# schematicCharger.net
KiCad netlist of a schematic drawn in Altium Designer
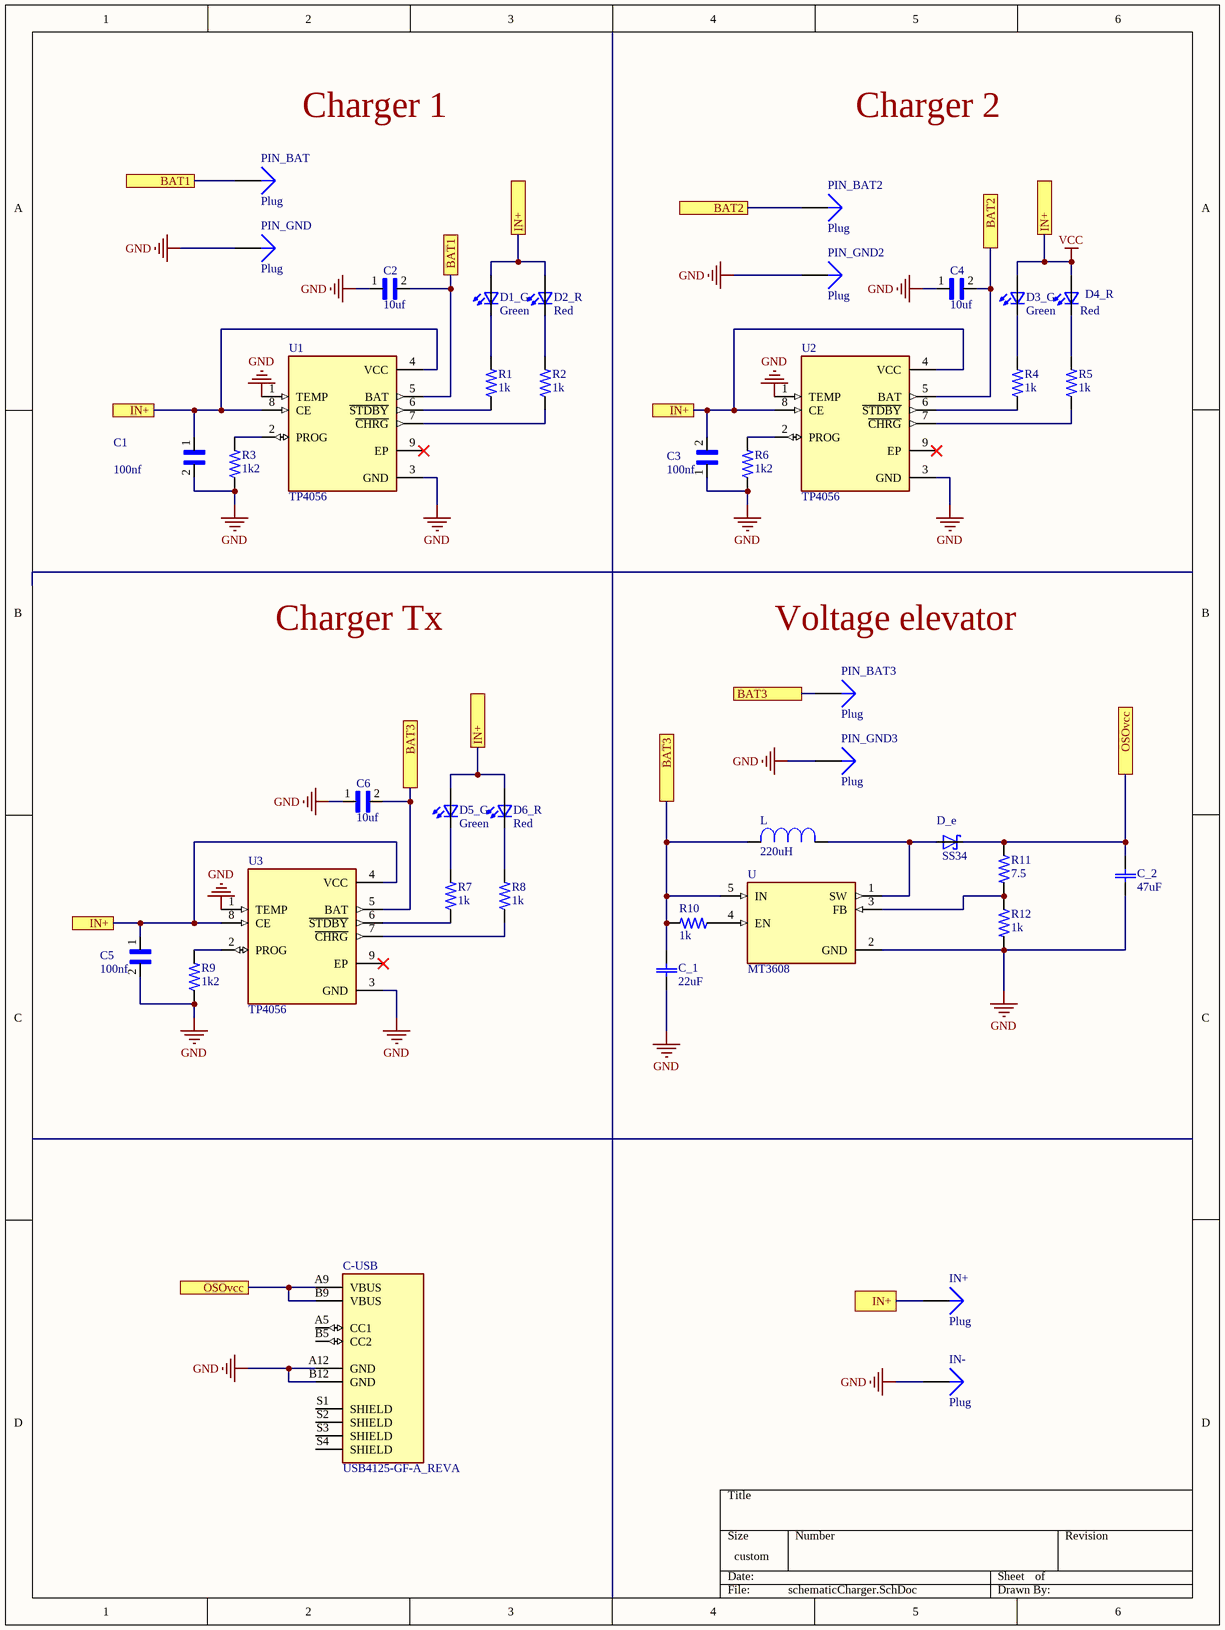
[diagram p0: schematicCharger.SchDoc]

(export (version "E")
  (design (tool "Eeschema 10.0.6"))
  (components
    (comp (ref "C-USB")
      (value "USB4125-GF-A_REVA")
      (footprint "GCT_USB4125-GF-A_REVA")
      (description "USB 2.0 Type C Receptacle, Horizontal, SMT, For Power charging")
      (fields (field (name "MP") "USB4125-GF-A") (field (name "MF") "Global Connector Technology"))
      (libsource (lib "TipoC") (part "USB4125-GF-A_REVA"))
    )
    (comp (ref "C1")
      (value "100nf")
      (footprint "CAPC1608X90")
      (description "0.1ÂµF Â±10% 50V Ceramic Capacitor X7R 0603 _1608 Metric_")
      (fields (field (name "DIGI-KEY_PART_NUMBER") "311-1344-1-ND") (field (name "MP") "CC0603KRX7R9BB104"))
      (libsource (lib "") (part "CC0603KRX7R9BB104_2"))
    )
    (comp (ref "C2")
      (value "10uf")
      (footprint "CAPC1608X90")
      (description "0.1ÂµF Â±10% 50V Ceramic Capacitor X7R 0603 _1608 Metric_")
      (fields (field (name "DIGI-KEY_PART_NUMBER") "311-1344-1-ND") (field (name "MP") "CC0603KRX7R9BB104"))
      (libsource (lib "capacitor0603") (part "CC0603KRX7R9BB104"))
    )
    (comp (ref "C3")
      (value "100nf")
      (footprint "CAPC1608X90")
      (description "0.1ÂµF Â±10% 50V Ceramic Capacitor X7R 0603 _1608 Metric_")
      (fields (field (name "DIGI-KEY_PART_NUMBER") "311-1344-1-ND") (field (name "MP") "CC0603KRX7R9BB104"))
      (libsource (lib "") (part "CC0603KRX7R9BB104_1"))
    )
    (comp (ref "C4")
      (value "10uf")
      (footprint "CAPC1608X90")
      (description "0.1ÂµF Â±10% 50V Ceramic Capacitor X7R 0603 _1608 Metric_")
      (fields (field (name "DIGI-KEY_PART_NUMBER") "311-1344-1-ND") (field (name "MP") "CC0603KRX7R9BB104"))
      (libsource (lib "capacitor0603") (part "CC0603KRX7R9BB104"))
    )
    (comp (ref "C5")
      (value "100nf")
      (footprint "CAPC1608X90")
      (description "0.1ÂµF Â±10% 50V Ceramic Capacitor X7R 0603 _1608 Metric_")
      (fields (field (name "DIGI-KEY_PART_NUMBER") "311-1344-1-ND") (field (name "MP") "CC0603KRX7R9BB104"))
      (libsource (lib "") (part "CC0603KRX7R9BB104_2"))
    )
    (comp (ref "C6")
      (value "10uf")
      (footprint "CAPC1608X90")
      (description "0.1ÂµF Â±10% 50V Ceramic Capacitor X7R 0603 _1608 Metric_")
      (fields (field (name "DIGI-KEY_PART_NUMBER") "311-1344-1-ND") (field (name "MP") "CC0603KRX7R9BB104"))
      (libsource (lib "capacitor0603") (part "CC0603KRX7R9BB104"))
    )
    (comp (ref "C_1")
      (value "22uF")
      (footprint "CAPC4532X254N")
      (description "0.33ÂµF Â±10% 250V Ceramic Capacitor X7R 1812 (4532 Metric)")
      (fields (field (name "MF") "AVX") (field (name "MP") "1812PC334KAT1A"))
      (libsource (lib "1812_CAP") (part "1812PC334KAT1A"))
    )
    (comp (ref "C_2")
      (value "47uF")
      (footprint "CAPC4532X254N")
      (description "0.33ÂµF Â±10% 250V Ceramic Capacitor X7R 1812 (4532 Metric)")
      (fields (field (name "MF") "AVX") (field (name "MP") "1812PC334KAT1A"))
      (libsource (lib "1812_CAP") (part "1812PC334KAT1A"))
    )
    (comp (ref "D1_G")
      (value "Green")
      (footprint "0603gree")
      (description "Green 571nm LED Indication - Discrete 2V 0603 _1608 Metric_")
      (fields (field (name "MF") "Lite-On Inc.") (field (name "MP") "LTST-C191KGKT"))
      (libsource (lib "LedVerde") (part "LTST-C191KGKT"))
    )
    (comp (ref "D2_R")
      (value "Red")
      (footprint "0603red")
      (description "Green 571nm LED Indication - Discrete 2V 0603 _1608 Metric_")
      (fields (field (name "MF") "Lite-On Inc.") (field (name "MP") "LTST-C191KGKT"))
      (libsource (lib "LedRojo") (part "LTST-C191KGKT"))
    )
    (comp (ref "D3_G")
      (value "Green")
      (footprint "0603gree")
      (description "Green 571nm LED Indication - Discrete 2V 0603 _1608 Metric_")
      (fields (field (name "MF") "Lite-On Inc.") (field (name "MP") "LTST-C191KGKT"))
      (libsource (lib "LedVerde") (part "LTST-C191KGKT"))
    )
    (comp (ref "D4_R")
      (value "Red")
      (footprint "0603red")
      (description "Green 571nm LED Indication - Discrete 2V 0603 _1608 Metric_")
      (fields (field (name "MF") "Lite-On Inc.") (field (name "MP") "LTST-C191KGKT"))
      (libsource (lib "LedRojo") (part "LTST-C191KGKT"))
    )
    (comp (ref "D5_G")
      (value "Green")
      (footprint "0603gree")
      (description "Green 571nm LED Indication - Discrete 2V 0603 _1608 Metric_")
      (fields (field (name "MF") "Lite-On Inc.") (field (name "MP") "LTST-C191KGKT"))
      (libsource (lib "LedVerde") (part "LTST-C191KGKT"))
    )
    (comp (ref "D6_R")
      (value "Red")
      (footprint "0603red")
      (description "Green 571nm LED Indication - Discrete 2V 0603 _1608 Metric_")
      (fields (field (name "MF") "Lite-On Inc.") (field (name "MP") "LTST-C191KGKT"))
      (libsource (lib "LedRojo") (part "LTST-C191KGKT"))
    )
    (comp (ref "D_e")
      (value "SS34")
      (footprint "DIOM6859X262N")
      (fields (field (name "MF") "ON Semiconductor"))
      (libsource (lib "ss34v3") (part "SS34"))
    )
    (comp (ref "IN+")
      (value "Plug")
      (footprint "PIN1")
      (fields (field (name "PUBLISHER") "Altium Limited"))
      (libsource (lib "Miscellaneous Connectors") (part "Plug"))
    )
    (comp (ref "IN-")
      (value "Plug")
      (footprint "PIN1")
      (fields (field (name "PUBLISHER") "Altium Limited"))
      (libsource (lib "Miscellaneous Connectors") (part "Plug"))
    )
    (comp (ref "L")
      (value "220uH")
      (footprint "INDM7676X435N")
      (description "2.2ÂµH Shielded Wirewound Inductor 4.76A 12.6mOhm Nonstandard")
      (fields (field (name "MP") "DR74-2R2-R") (field (name "MF") "Eaton"))
      (libsource (lib "Bobina220") (part "DR74-2R2-R"))
    )
    (comp (ref "PIN_BAT")
      (value "Plug")
      (footprint "PIN1")
      (fields (field (name "PUBLISHER") "Altium Limited"))
      (libsource (lib "Miscellaneous Connectors") (part "Plug"))
    )
    (comp (ref "PIN_BAT2")
      (value "Plug")
      (footprint "PIN1")
      (fields (field (name "PUBLISHER") "Altium Limited"))
      (libsource (lib "Miscellaneous Connectors") (part "Plug"))
    )
    (comp (ref "PIN_BAT3")
      (value "Plug")
      (footprint "PIN1")
      (fields (field (name "PUBLISHER") "Altium Limited"))
      (libsource (lib "Miscellaneous Connectors") (part "Plug"))
    )
    (comp (ref "PIN_GND")
      (value "Plug")
      (footprint "PIN1")
      (fields (field (name "PUBLISHER") "Altium Limited"))
      (libsource (lib "Miscellaneous Connectors") (part "Plug"))
    )
    (comp (ref "PIN_GND2")
      (value "Plug")
      (footprint "PIN1")
      (fields (field (name "PUBLISHER") "Altium Limited"))
      (libsource (lib "Miscellaneous Connectors") (part "Plug"))
    )
    (comp (ref "PIN_GND3")
      (value "Plug")
      (footprint "PIN1")
      (fields (field (name "PUBLISHER") "Altium Limited"))
      (libsource (lib "Miscellaneous Connectors") (part "Plug"))
    )
    (comp (ref "R1")
      (value "1k")
      (footprint "RESC1608X50N")
      (description "Res, Thin Film, 13r, 0.1%, 0.1w, 0603")
      (fields (field (name "MP") "RP73D1J13RBTDG") (field (name "MF") "TE Connectivity"))
      (libsource (lib "Res0603") (part "RP73D1J13RBTDG"))
    )
    (comp (ref "R2")
      (value "1k")
      (footprint "RESC1608X50N")
      (description "Res, Thin Film, 13r, 0.1%, 0.1w, 0603")
      (fields (field (name "MP") "RP73D1J13RBTDG") (field (name "MF") "TE Connectivity"))
      (libsource (lib "Res0603") (part "RP73D1J13RBTDG"))
    )
    (comp (ref "R3")
      (value "1k2")
      (footprint "RESC1608X50N")
      (description "Res, Thin Film, 13r, 0.1%, 0.1w, 0603")
      (fields (field (name "MP") "RP73D1J13RBTDG") (field (name "MF") "TE Connectivity"))
      (libsource (lib "Res0603") (part "RP73D1J13RBTDG"))
    )
    (comp (ref "R4")
      (value "1k")
      (footprint "RESC1608X50N")
      (description "Res, Thin Film, 13r, 0.1%, 0.1w, 0603")
      (fields (field (name "MP") "RP73D1J13RBTDG") (field (name "MF") "TE Connectivity"))
      (libsource (lib "Res0603") (part "RP73D1J13RBTDG"))
    )
    (comp (ref "R5")
      (value "1k")
      (footprint "RESC1608X50N")
      (description "Res, Thin Film, 13r, 0.1%, 0.1w, 0603")
      (fields (field (name "MP") "RP73D1J13RBTDG") (field (name "MF") "TE Connectivity"))
      (libsource (lib "Res0603") (part "RP73D1J13RBTDG"))
    )
    (comp (ref "R6")
      (value "1k2")
      (footprint "RESC1608X50N")
      (description "Res, Thin Film, 13r, 0.1%, 0.1w, 0603")
      (fields (field (name "MP") "RP73D1J13RBTDG") (field (name "MF") "TE Connectivity"))
      (libsource (lib "Res0603") (part "RP73D1J13RBTDG"))
    )
    (comp (ref "R7")
      (value "1k")
      (footprint "RESC1608X50N")
      (description "Res, Thin Film, 13r, 0.1%, 0.1w, 0603")
      (fields (field (name "MP") "RP73D1J13RBTDG") (field (name "MF") "TE Connectivity"))
      (libsource (lib "Res0603") (part "RP73D1J13RBTDG"))
    )
    (comp (ref "R8")
      (value "1k")
      (footprint "RESC1608X50N")
      (description "Res, Thin Film, 13r, 0.1%, 0.1w, 0603")
      (fields (field (name "MP") "RP73D1J13RBTDG") (field (name "MF") "TE Connectivity"))
      (libsource (lib "Res0603") (part "RP73D1J13RBTDG"))
    )
    (comp (ref "R9")
      (value "1k2")
      (footprint "RESC1608X50N")
      (description "Res, Thin Film, 13r, 0.1%, 0.1w, 0603")
      (fields (field (name "MP") "RP73D1J13RBTDG") (field (name "MF") "TE Connectivity"))
      (libsource (lib "Res0603") (part "RP73D1J13RBTDG"))
    )
    (comp (ref "R10")
      (value "1k")
      (footprint "RESC1608X50N")
      (description "Res, Thin Film, 13r, 0.1%, 0.1w, 0603")
      (fields (field (name "MP") "RP73D1J13RBTDG") (field (name "MF") "TE Connectivity"))
      (libsource (lib "Res0603") (part "RP73D1J13RBTDG"))
    )
    (comp (ref "R11")
      (value "7.5")
      (footprint "RESC1608X50N")
      (description "Res, Thin Film, 13r, 0.1%, 0.1w, 0603")
      (fields (field (name "MP") "RP73D1J13RBTDG") (field (name "MF") "TE Connectivity"))
      (libsource (lib "Res0603") (part "RP73D1J13RBTDG"))
    )
    (comp (ref "R12")
      (value "1k")
      (footprint "RESC1608X50N")
      (description "Res, Thin Film, 13r, 0.1%, 0.1w, 0603")
      (fields (field (name "MP") "RP73D1J13RBTDG") (field (name "MF") "TE Connectivity"))
      (libsource (lib "Res0603") (part "RP73D1J13RBTDG"))
    )
    (comp (ref "U")
      (value "MT3608")
      (footprint "SOT95P280X145-6N")
      (description "High Efficiency 1.2MHz2A Step Up Converter")
      (fields (field (name "MF") "Aerosemi Technology Co., Ltd"))
      (libsource (lib "MT3608") (part "MT3608"))
    )
    (comp (ref "U1")
      (value "TP4056")
      (footprint "SOP127P600X175-9N")
      (description "Complete single cell Li-Ion battery with a constant current / constant voltage linear charger")
      (fields (field (name "MF") "NanJing Top Power ASIC Corp."))
      (libsource (lib "TP4056") (part "TP4056"))
    )
    (comp (ref "U2")
      (value "TP4056")
      (footprint "SOP127P600X175-9N")
      (description "Complete single cell Li-Ion battery with a constant current / constant voltage linear charger")
      (fields (field (name "MF") "NanJing Top Power ASIC Corp."))
      (libsource (lib "TP4056") (part "TP4056"))
    )
    (comp (ref "U3")
      (value "TP4056")
      (footprint "SOP127P600X175-9N")
      (description "Complete single cell Li-Ion battery with a constant current / constant voltage linear charger")
      (fields (field (name "MF") "NanJing Top Power ASIC Corp."))
      (libsource (lib "TP4056") (part "TP4056"))
    )
  )
  (nets
    (net (code "1") (name "/BAT1") (class "Default")
      (node (ref "C2") (pin "2") (pinfunction "2_2") (pintype "passive"))
      (node (ref "PIN_BAT") (pin "1") (pinfunction "1_1") (pintype "passive"))
      (node (ref "U1") (pin "5") (pinfunction "BAT_5") (pintype "output"))
    )
    (net (code "2") (name "/BAT2") (class "Default")
      (node (ref "C4") (pin "2") (pinfunction "2_2") (pintype "passive"))
      (node (ref "PIN_BAT2") (pin "1") (pinfunction "1_1") (pintype "passive"))
      (node (ref "U2") (pin "5") (pinfunction "BAT_5") (pintype "output"))
    )
    (net (code "3") (name "/BAT3") (class "Default")
      (node (ref "C6") (pin "2") (pinfunction "2_2") (pintype "passive"))
      (node (ref "C_1") (pin "2") (pinfunction "C2_2") (pintype "passive"))
      (node (ref "L") (pin "2") (pinfunction "2_2") (pintype "passive"))
      (node (ref "PIN_BAT3") (pin "1") (pinfunction "1_1") (pintype "passive"))
      (node (ref "R10") (pin "2") (pinfunction "2_2") (pintype "passive"))
      (node (ref "U") (pin "5") (pinfunction "IN_5") (pintype "input"))
      (node (ref "U3") (pin "5") (pinfunction "BAT_5") (pintype "output"))
    )
    (net (code "4") (name "/OSOvcc") (class "Default")
      (node (ref "C-USB") (pin "A9") (pinfunction "VBUS_A9") (pintype "power_in"))
      (node (ref "C-USB") (pin "B9") (pinfunction "VBUS_B9") (pintype "power_in"))
      (node (ref "C_2") (pin "2") (pinfunction "C2_2") (pintype "passive"))
      (node (ref "D_e") (pin "C") (pinfunction "C_C") (pintype "passive"))
      (node (ref "R11") (pin "1") (pinfunction "1_1") (pintype "passive"))
    )
    (net (code "5") (name "GND") (class "Default")
      (node (ref "C-USB") (pin "A12") (pinfunction "GND_A12") (pintype "power_in"))
      (node (ref "C-USB") (pin "B12") (pinfunction "GND_B12") (pintype "power_in"))
      (node (ref "C1") (pin "2") (pinfunction "2_2") (pintype "passive"))
      (node (ref "C2") (pin "1") (pinfunction "1_1") (pintype "passive"))
      (node (ref "C3") (pin "1") (pinfunction "1_1") (pintype "passive"))
      (node (ref "C4") (pin "1") (pinfunction "1_1") (pintype "passive"))
      (node (ref "C5") (pin "2") (pinfunction "2_2") (pintype "passive"))
      (node (ref "C6") (pin "1") (pinfunction "1_1") (pintype "passive"))
      (node (ref "C_1") (pin "1") (pinfunction "C1_1") (pintype "passive"))
      (node (ref "C_2") (pin "1") (pinfunction "C1_1") (pintype "passive"))
      (node (ref "IN-") (pin "1") (pinfunction "1_1") (pintype "passive"))
      (node (ref "PIN_GND") (pin "1") (pinfunction "1_1") (pintype "passive"))
      (node (ref "PIN_GND2") (pin "1") (pinfunction "1_1") (pintype "passive"))
      (node (ref "PIN_GND3") (pin "1") (pinfunction "1_1") (pintype "passive"))
      (node (ref "R12") (pin "2") (pinfunction "2_2") (pintype "passive"))
      (node (ref "R3") (pin "1") (pinfunction "1_1") (pintype "passive"))
      (node (ref "R6") (pin "1") (pinfunction "1_1") (pintype "passive"))
      (node (ref "R9") (pin "1") (pinfunction "1_1") (pintype "passive"))
      (node (ref "U") (pin "2") (pinfunction "GND_2") (pintype "power_in"))
      (node (ref "U1") (pin "1") (pinfunction "TEMP_1") (pintype "input"))
      (node (ref "U1") (pin "3") (pinfunction "GND_3") (pintype "power_in"))
      (node (ref "U2") (pin "1") (pinfunction "TEMP_1") (pintype "input"))
      (node (ref "U2") (pin "3") (pinfunction "GND_3") (pintype "power_in"))
      (node (ref "U3") (pin "1") (pinfunction "TEMP_1") (pintype "input"))
      (node (ref "U3") (pin "3") (pinfunction "GND_3") (pintype "power_in"))
    )
    (net (code "6") (name "Net-(D1_G-K2)") (class "Default")
      (node (ref "D1_G") (pin "1") (pinfunction "K2_1") (pintype "passive"))
      (node (ref "R1") (pin "2") (pinfunction "2_2") (pintype "passive"))
    )
    (net (code "7") (name "Net-(D2_R-K2)") (class "Default")
      (node (ref "D2_R") (pin "1") (pinfunction "K2_1") (pintype "passive"))
      (node (ref "R2") (pin "2") (pinfunction "2_2") (pintype "passive"))
    )
    (net (code "8") (name "Net-(D3_G-K2)") (class "Default")
      (node (ref "D3_G") (pin "1") (pinfunction "K2_1") (pintype "passive"))
      (node (ref "R4") (pin "2") (pinfunction "2_2") (pintype "passive"))
    )
    (net (code "9") (name "Net-(D4_R-K2)") (class "Default")
      (node (ref "D4_R") (pin "1") (pinfunction "K2_1") (pintype "passive"))
      (node (ref "R5") (pin "2") (pinfunction "2_2") (pintype "passive"))
    )
    (net (code "10") (name "Net-(D5_G-K2)") (class "Default")
      (node (ref "D5_G") (pin "1") (pinfunction "K2_1") (pintype "passive"))
      (node (ref "R7") (pin "2") (pinfunction "2_2") (pintype "passive"))
    )
    (net (code "11") (name "Net-(D6_R-K2)") (class "Default")
      (node (ref "D6_R") (pin "1") (pinfunction "K2_1") (pintype "passive"))
      (node (ref "R8") (pin "2") (pinfunction "2_2") (pintype "passive"))
    )
    (net (code "12") (name "Net-(U-EN)") (class "Default")
      (node (ref "R10") (pin "1") (pinfunction "1_1") (pintype "passive"))
      (node (ref "U") (pin "4") (pinfunction "EN_4") (pintype "input"))
    )
    (net (code "13") (name "Net-(U-FB)") (class "Default")
      (node (ref "R11") (pin "2") (pinfunction "2_2") (pintype "passive"))
      (node (ref "R12") (pin "1") (pinfunction "1_1") (pintype "passive"))
      (node (ref "U") (pin "3") (pinfunction "FB_3") (pintype "input"))
    )
    (net (code "14") (name "Net-(U-SW)") (class "Default")
      (node (ref "D_e") (pin "A") (pinfunction "A_A") (pintype "passive"))
      (node (ref "L") (pin "1") (pinfunction "1_1") (pintype "passive"))
      (node (ref "U") (pin "1") (pinfunction "SW_1") (pintype "output"))
    )
    (net (code "15") (name "Net-(U1-PROG)") (class "Default")
      (node (ref "R3") (pin "2") (pinfunction "2_2") (pintype "passive"))
      (node (ref "U1") (pin "2") (pinfunction "PROG_2") (pintype "bidirectional"))
    )
    (net (code "16") (name "Net-(U1-~{CHRG})") (class "Default")
      (node (ref "R2") (pin "1") (pinfunction "1_1") (pintype "passive"))
      (node (ref "U1") (pin "7") (pinfunction "~{CHRG}_7") (pintype "output"))
    )
    (net (code "17") (name "Net-(U1-~{STDBY})") (class "Default")
      (node (ref "R1") (pin "1") (pinfunction "1_1") (pintype "passive"))
      (node (ref "U1") (pin "6") (pinfunction "~{STDBY}_6") (pintype "output"))
    )
    (net (code "18") (name "Net-(U2-PROG)") (class "Default")
      (node (ref "R6") (pin "2") (pinfunction "2_2") (pintype "passive"))
      (node (ref "U2") (pin "2") (pinfunction "PROG_2") (pintype "bidirectional"))
    )
    (net (code "19") (name "Net-(U2-~{CHRG})") (class "Default")
      (node (ref "R5") (pin "1") (pinfunction "1_1") (pintype "passive"))
      (node (ref "U2") (pin "7") (pinfunction "~{CHRG}_7") (pintype "output"))
    )
    (net (code "20") (name "Net-(U2-~{STDBY})") (class "Default")
      (node (ref "R4") (pin "1") (pinfunction "1_1") (pintype "passive"))
      (node (ref "U2") (pin "6") (pinfunction "~{STDBY}_6") (pintype "output"))
    )
    (net (code "21") (name "Net-(U3-PROG)") (class "Default")
      (node (ref "R9") (pin "2") (pinfunction "2_2") (pintype "passive"))
      (node (ref "U3") (pin "2") (pinfunction "PROG_2") (pintype "bidirectional"))
    )
    (net (code "22") (name "Net-(U3-~{CHRG})") (class "Default")
      (node (ref "R8") (pin "1") (pinfunction "1_1") (pintype "passive"))
      (node (ref "U3") (pin "7") (pinfunction "~{CHRG}_7") (pintype "output"))
    )
    (net (code "23") (name "Net-(U3-~{STDBY})") (class "Default")
      (node (ref "R7") (pin "1") (pinfunction "1_1") (pintype "passive"))
      (node (ref "U3") (pin "6") (pinfunction "~{STDBY}_6") (pintype "output"))
    )
    (net (code "24") (name "VCC") (class "Default")
      (node (ref "C1") (pin "1") (pinfunction "1_1") (pintype "passive"))
      (node (ref "C3") (pin "2") (pinfunction "2_2") (pintype "passive"))
      (node (ref "C5") (pin "1") (pinfunction "1_1") (pintype "passive"))
      (node (ref "D1_G") (pin "2") (pinfunction "A2_2") (pintype "passive"))
      (node (ref "D2_R") (pin "2") (pinfunction "A2_2") (pintype "passive"))
      (node (ref "D3_G") (pin "2") (pinfunction "A2_2") (pintype "passive"))
      (node (ref "D4_R") (pin "2") (pinfunction "A2_2") (pintype "passive"))
      (node (ref "D5_G") (pin "2") (pinfunction "A2_2") (pintype "passive"))
      (node (ref "D6_R") (pin "2") (pinfunction "A2_2") (pintype "passive"))
      (node (ref "IN+") (pin "1") (pinfunction "1_1") (pintype "passive"))
      (node (ref "U1") (pin "4") (pinfunction "VCC_4") (pintype "power_in"))
      (node (ref "U1") (pin "8") (pinfunction "CE_8") (pintype "input"))
      (node (ref "U2") (pin "4") (pinfunction "VCC_4") (pintype "power_in"))
      (node (ref "U2") (pin "8") (pinfunction "CE_8") (pintype "input"))
      (node (ref "U3") (pin "4") (pinfunction "VCC_4") (pintype "power_in"))
      (node (ref "U3") (pin "8") (pinfunction "CE_8") (pintype "input"))
    )
    (net (code "25") (name "unconnected-(C-USB-CC1-PadA5)") (class "Default")
      (node (ref "C-USB") (pin "A5") (pinfunction "CC1_A5") (pintype "bidirectional"))
    )
    (net (code "26") (name "unconnected-(C-USB-CC2-PadB5)") (class "Default")
      (node (ref "C-USB") (pin "B5") (pinfunction "CC2_B5") (pintype "bidirectional"))
    )
    (net (code "27") (name "unconnected-(C-USB-SHIELD-PadS1)") (class "Default")
      (node (ref "C-USB") (pin "S1") (pinfunction "SHIELD_S1") (pintype "passive"))
    )
    (net (code "28") (name "unconnected-(C-USB-SHIELD-PadS2)") (class "Default")
      (node (ref "C-USB") (pin "S2") (pinfunction "SHIELD_S2") (pintype "passive"))
    )
    (net (code "29") (name "unconnected-(C-USB-SHIELD-PadS3)") (class "Default")
      (node (ref "C-USB") (pin "S3") (pinfunction "SHIELD_S3") (pintype "passive"))
    )
    (net (code "30") (name "unconnected-(C-USB-SHIELD-PadS4)") (class "Default")
      (node (ref "C-USB") (pin "S4") (pinfunction "SHIELD_S4") (pintype "passive"))
    )
    (net (code "31") (name "unconnected-(U1-EP-Pad9)") (class "Default")
      (node (ref "U1") (pin "9") (pinfunction "EP_9") (pintype "passive+no_connect"))
    )
    (net (code "32") (name "unconnected-(U2-EP-Pad9)") (class "Default")
      (node (ref "U2") (pin "9") (pinfunction "EP_9") (pintype "passive+no_connect"))
    )
    (net (code "33") (name "unconnected-(U3-EP-Pad9)") (class "Default")
      (node (ref "U3") (pin "9") (pinfunction "EP_9") (pintype "passive+no_connect"))
    )
  )
)
